# LEDs.net
KiCad netlist of a schematic drawn in Altium Designer
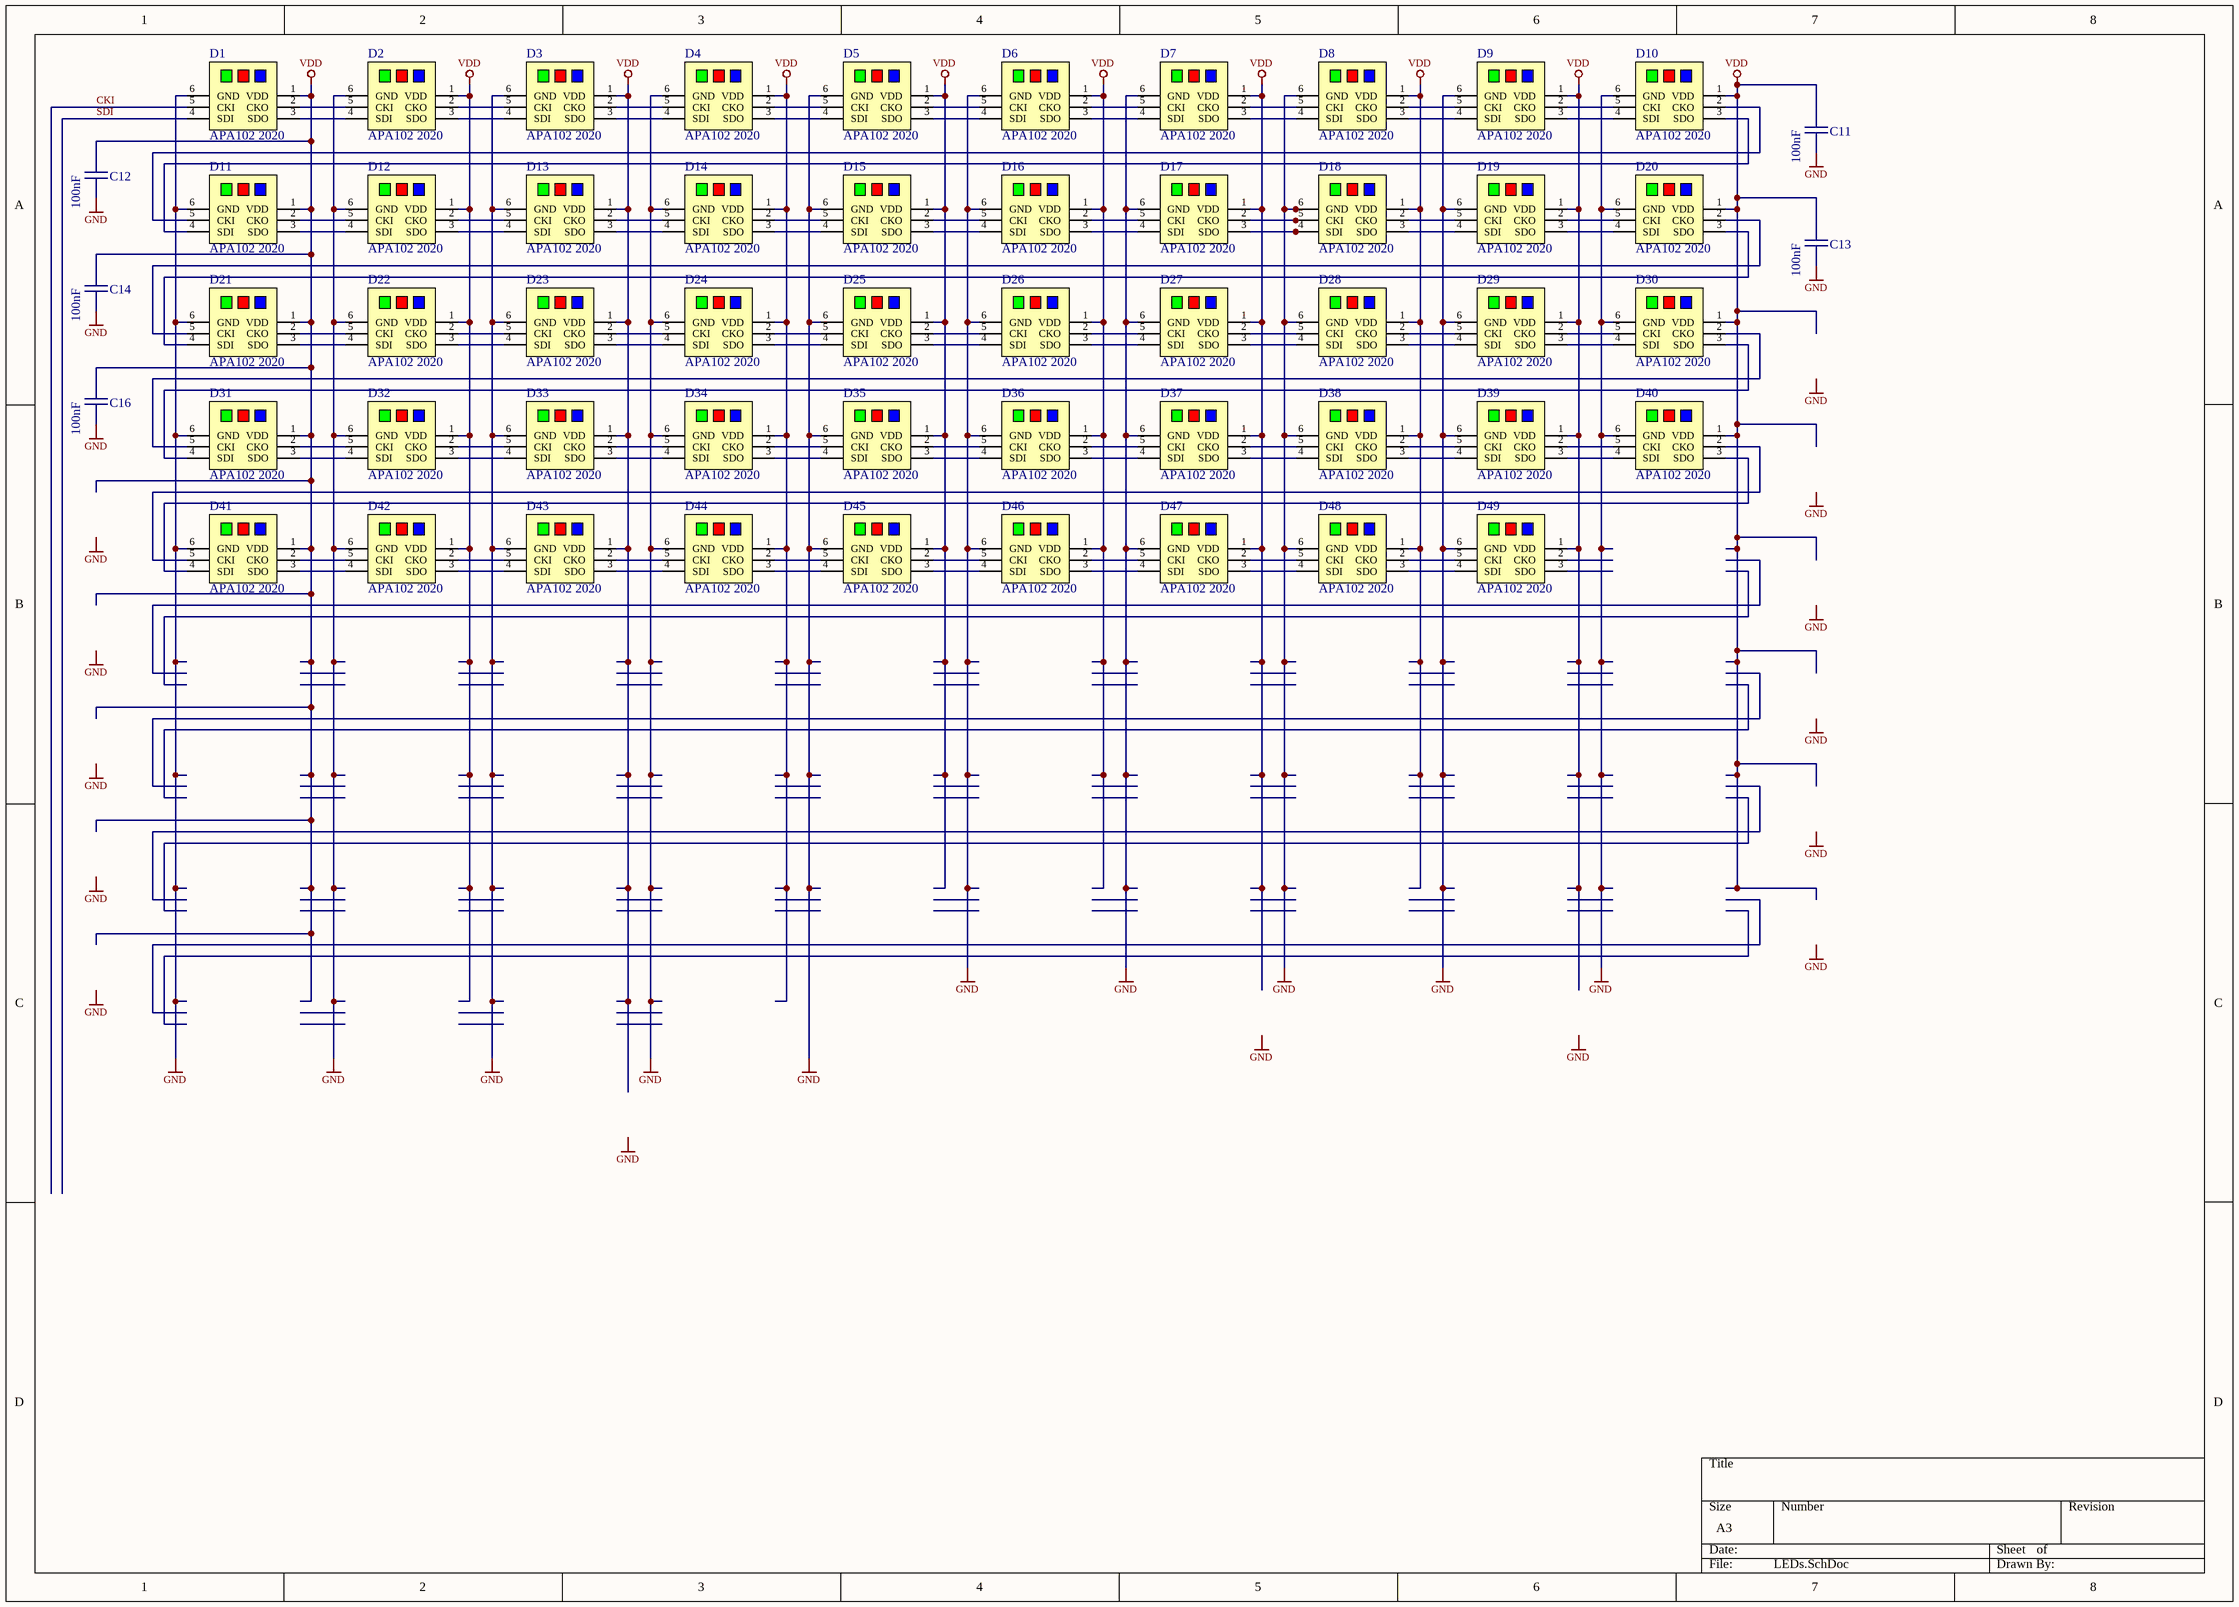
[diagram p0: LEDs.SchDoc]

(export (version "E")
  (design (tool "Eeschema 10.0.6"))
  (components
    (comp (ref "C11")
      (value "100nF")
      (footprint "CAPC0603(1608)55_N")
      (libsource (lib "OVLib_64") (part "CAP"))
    )
    (comp (ref "C12")
      (value "100nF")
      (footprint "CAPC0603(1608)55_N")
      (libsource (lib "OVLib_64") (part "CAP"))
    )
    (comp (ref "C13")
      (value "100nF")
      (footprint "CAPC0603(1608)55_N")
      (libsource (lib "OVLib_64") (part "CAP"))
    )
    (comp (ref "C14")
      (value "100nF")
      (footprint "CAPC0603(1608)55_N")
      (libsource (lib "OVLib_64") (part "CAP"))
    )
    (comp (ref "C16")
      (value "100nF")
      (footprint "CAPC0603(1608)55_N")
      (libsource (lib "OVLib_64") (part "CAP"))
    )
    (comp (ref "D1")
      (value "APA102 2020")
      (footprint "APA_RGB_LED_2020")
      (libsource (lib "OVLib_64") (part "LED_RGB_APA102"))
    )
    (comp (ref "D2")
      (value "APA102 2020")
      (footprint "APA_RGB_LED_2020")
      (libsource (lib "OVLib_64") (part "LED_RGB_APA102"))
    )
    (comp (ref "D3")
      (value "APA102 2020")
      (footprint "APA_RGB_LED_2020")
      (libsource (lib "OVLib_64") (part "LED_RGB_APA102"))
    )
    (comp (ref "D4")
      (value "APA102 2020")
      (footprint "APA_RGB_LED_2020")
      (libsource (lib "OVLib_64") (part "LED_RGB_APA102"))
    )
    (comp (ref "D5")
      (value "APA102 2020")
      (footprint "APA_RGB_LED_2020")
      (libsource (lib "OVLib_64") (part "LED_RGB_APA102"))
    )
    (comp (ref "D6")
      (value "APA102 2020")
      (footprint "APA_RGB_LED_2020")
      (libsource (lib "OVLib_64") (part "LED_RGB_APA102"))
    )
    (comp (ref "D7")
      (value "APA102 2020")
      (footprint "APA_RGB_LED_2020")
      (libsource (lib "OVLib_64") (part "LED_RGB_APA102"))
    )
    (comp (ref "D8")
      (value "APA102 2020")
      (footprint "APA_RGB_LED_2020")
      (libsource (lib "OVLib_64") (part "LED_RGB_APA102"))
    )
    (comp (ref "D9")
      (value "APA102 2020")
      (footprint "APA_RGB_LED_2020")
      (libsource (lib "OVLib_64") (part "LED_RGB_APA102"))
    )
    (comp (ref "D10")
      (value "APA102 2020")
      (footprint "APA_RGB_LED_2020")
      (libsource (lib "OVLib_64") (part "LED_RGB_APA102"))
    )
    (comp (ref "D11")
      (value "APA102 2020")
      (footprint "APA_RGB_LED_2020")
      (libsource (lib "OVLib_64") (part "LED_RGB_APA102"))
    )
    (comp (ref "D12")
      (value "APA102 2020")
      (footprint "APA_RGB_LED_2020")
      (libsource (lib "OVLib_64") (part "LED_RGB_APA102"))
    )
    (comp (ref "D13")
      (value "APA102 2020")
      (footprint "APA_RGB_LED_2020")
      (libsource (lib "OVLib_64") (part "LED_RGB_APA102"))
    )
    (comp (ref "D14")
      (value "APA102 2020")
      (footprint "APA_RGB_LED_2020")
      (libsource (lib "OVLib_64") (part "LED_RGB_APA102"))
    )
    (comp (ref "D15")
      (value "APA102 2020")
      (footprint "APA_RGB_LED_2020")
      (libsource (lib "OVLib_64") (part "LED_RGB_APA102"))
    )
    (comp (ref "D16")
      (value "APA102 2020")
      (footprint "APA_RGB_LED_2020")
      (libsource (lib "OVLib_64") (part "LED_RGB_APA102"))
    )
    (comp (ref "D17")
      (value "APA102 2020")
      (footprint "APA_RGB_LED_2020")
      (libsource (lib "OVLib_64") (part "LED_RGB_APA102"))
    )
    (comp (ref "D18")
      (value "APA102 2020")
      (footprint "APA_RGB_LED_2020")
      (libsource (lib "OVLib_64") (part "LED_RGB_APA102"))
    )
    (comp (ref "D19")
      (value "APA102 2020")
      (footprint "APA_RGB_LED_2020")
      (libsource (lib "OVLib_64") (part "LED_RGB_APA102"))
    )
    (comp (ref "D20")
      (value "APA102 2020")
      (footprint "APA_RGB_LED_2020")
      (libsource (lib "OVLib_64") (part "LED_RGB_APA102"))
    )
    (comp (ref "D21")
      (value "APA102 2020")
      (footprint "APA_RGB_LED_2020")
      (libsource (lib "OVLib_64") (part "LED_RGB_APA102"))
    )
    (comp (ref "D22")
      (value "APA102 2020")
      (footprint "APA_RGB_LED_2020")
      (libsource (lib "OVLib_64") (part "LED_RGB_APA102"))
    )
    (comp (ref "D23")
      (value "APA102 2020")
      (footprint "APA_RGB_LED_2020")
      (libsource (lib "OVLib_64") (part "LED_RGB_APA102"))
    )
    (comp (ref "D24")
      (value "APA102 2020")
      (footprint "APA_RGB_LED_2020")
      (libsource (lib "OVLib_64") (part "LED_RGB_APA102"))
    )
    (comp (ref "D25")
      (value "APA102 2020")
      (footprint "APA_RGB_LED_2020")
      (libsource (lib "OVLib_64") (part "LED_RGB_APA102"))
    )
    (comp (ref "D26")
      (value "APA102 2020")
      (footprint "APA_RGB_LED_2020")
      (libsource (lib "OVLib_64") (part "LED_RGB_APA102"))
    )
    (comp (ref "D27")
      (value "APA102 2020")
      (footprint "APA_RGB_LED_2020")
      (libsource (lib "OVLib_64") (part "LED_RGB_APA102"))
    )
    (comp (ref "D28")
      (value "APA102 2020")
      (footprint "APA_RGB_LED_2020")
      (libsource (lib "OVLib_64") (part "LED_RGB_APA102"))
    )
    (comp (ref "D29")
      (value "APA102 2020")
      (footprint "APA_RGB_LED_2020")
      (libsource (lib "OVLib_64") (part "LED_RGB_APA102"))
    )
    (comp (ref "D30")
      (value "APA102 2020")
      (footprint "APA_RGB_LED_2020")
      (libsource (lib "OVLib_64") (part "LED_RGB_APA102"))
    )
    (comp (ref "D31")
      (value "APA102 2020")
      (footprint "APA_RGB_LED_2020")
      (libsource (lib "OVLib_64") (part "LED_RGB_APA102"))
    )
    (comp (ref "D32")
      (value "APA102 2020")
      (footprint "APA_RGB_LED_2020")
      (libsource (lib "OVLib_64") (part "LED_RGB_APA102"))
    )
    (comp (ref "D33")
      (value "APA102 2020")
      (footprint "APA_RGB_LED_2020")
      (libsource (lib "OVLib_64") (part "LED_RGB_APA102"))
    )
    (comp (ref "D34")
      (value "APA102 2020")
      (footprint "APA_RGB_LED_2020")
      (libsource (lib "OVLib_64") (part "LED_RGB_APA102"))
    )
    (comp (ref "D35")
      (value "APA102 2020")
      (footprint "APA_RGB_LED_2020")
      (libsource (lib "OVLib_64") (part "LED_RGB_APA102"))
    )
    (comp (ref "D36")
      (value "APA102 2020")
      (footprint "APA_RGB_LED_2020")
      (libsource (lib "OVLib_64") (part "LED_RGB_APA102"))
    )
    (comp (ref "D37")
      (value "APA102 2020")
      (footprint "APA_RGB_LED_2020")
      (libsource (lib "OVLib_64") (part "LED_RGB_APA102"))
    )
    (comp (ref "D38")
      (value "APA102 2020")
      (footprint "APA_RGB_LED_2020")
      (libsource (lib "OVLib_64") (part "LED_RGB_APA102"))
    )
    (comp (ref "D39")
      (value "APA102 2020")
      (footprint "APA_RGB_LED_2020")
      (libsource (lib "OVLib_64") (part "LED_RGB_APA102"))
    )
    (comp (ref "D40")
      (value "APA102 2020")
      (footprint "APA_RGB_LED_2020")
      (libsource (lib "OVLib_64") (part "LED_RGB_APA102"))
    )
    (comp (ref "D41")
      (value "APA102 2020")
      (footprint "APA_RGB_LED_2020")
      (libsource (lib "OVLib_64") (part "LED_RGB_APA102"))
    )
    (comp (ref "D42")
      (value "APA102 2020")
      (footprint "APA_RGB_LED_2020")
      (libsource (lib "OVLib_64") (part "LED_RGB_APA102"))
    )
    (comp (ref "D43")
      (value "APA102 2020")
      (footprint "APA_RGB_LED_2020")
      (libsource (lib "OVLib_64") (part "LED_RGB_APA102"))
    )
    (comp (ref "D44")
      (value "APA102 2020")
      (footprint "APA_RGB_LED_2020")
      (libsource (lib "OVLib_64") (part "LED_RGB_APA102"))
    )
    (comp (ref "D45")
      (value "APA102 2020")
      (footprint "APA_RGB_LED_2020")
      (libsource (lib "OVLib_64") (part "LED_RGB_APA102"))
    )
    (comp (ref "D46")
      (value "APA102 2020")
      (footprint "APA_RGB_LED_2020")
      (libsource (lib "OVLib_64") (part "LED_RGB_APA102"))
    )
    (comp (ref "D47")
      (value "APA102 2020")
      (footprint "APA_RGB_LED_2020")
      (libsource (lib "OVLib_64") (part "LED_RGB_APA102"))
    )
    (comp (ref "D48")
      (value "APA102 2020")
      (footprint "APA_RGB_LED_2020")
      (libsource (lib "OVLib_64") (part "LED_RGB_APA102"))
    )
    (comp (ref "D49")
      (value "APA102 2020")
      (footprint "APA_RGB_LED_2020")
      (libsource (lib "OVLib_64") (part "LED_RGB_APA102"))
    )
  )
  (nets
    (net (code "1") (name "/CKI") (class "Default")
      (node (ref "D1") (pin "5") (pinfunction "CKI_5") (pintype "passive"))
    )
    (net (code "2") (name "/SDI") (class "Default")
      (node (ref "D1") (pin "4") (pinfunction "SDI_4") (pintype "passive"))
    )
    (net (code "3") (name "GND") (class "Default")
      (node (ref "C11") (pin "1") (pinfunction "1_1") (pintype "passive"))
      (node (ref "C12") (pin "1") (pinfunction "1_1") (pintype "passive"))
      (node (ref "C13") (pin "1") (pinfunction "1_1") (pintype "passive"))
      (node (ref "C14") (pin "1") (pinfunction "1_1") (pintype "passive"))
      (node (ref "C16") (pin "1") (pinfunction "1_1") (pintype "passive"))
      (node (ref "D1") (pin "6") (pinfunction "GND_6") (pintype "passive"))
      (node (ref "D10") (pin "6") (pinfunction "GND_6") (pintype "passive"))
      (node (ref "D11") (pin "6") (pinfunction "GND_6") (pintype "passive"))
      (node (ref "D12") (pin "6") (pinfunction "GND_6") (pintype "passive"))
      (node (ref "D13") (pin "6") (pinfunction "GND_6") (pintype "passive"))
      (node (ref "D14") (pin "6") (pinfunction "GND_6") (pintype "passive"))
      (node (ref "D15") (pin "6") (pinfunction "GND_6") (pintype "passive"))
      (node (ref "D16") (pin "6") (pinfunction "GND_6") (pintype "passive"))
      (node (ref "D17") (pin "6") (pinfunction "GND_6") (pintype "passive"))
      (node (ref "D18") (pin "6") (pinfunction "GND_6") (pintype "passive"))
      (node (ref "D19") (pin "6") (pinfunction "GND_6") (pintype "passive"))
      (node (ref "D2") (pin "6") (pinfunction "GND_6") (pintype "passive"))
      (node (ref "D20") (pin "6") (pinfunction "GND_6") (pintype "passive"))
      (node (ref "D21") (pin "6") (pinfunction "GND_6") (pintype "passive"))
      (node (ref "D22") (pin "6") (pinfunction "GND_6") (pintype "passive"))
      (node (ref "D23") (pin "6") (pinfunction "GND_6") (pintype "passive"))
      (node (ref "D24") (pin "6") (pinfunction "GND_6") (pintype "passive"))
      (node (ref "D25") (pin "6") (pinfunction "GND_6") (pintype "passive"))
      (node (ref "D26") (pin "6") (pinfunction "GND_6") (pintype "passive"))
      (node (ref "D27") (pin "6") (pinfunction "GND_6") (pintype "passive"))
      (node (ref "D28") (pin "6") (pinfunction "GND_6") (pintype "passive"))
      (node (ref "D29") (pin "6") (pinfunction "GND_6") (pintype "passive"))
      (node (ref "D3") (pin "6") (pinfunction "GND_6") (pintype "passive"))
      (node (ref "D30") (pin "6") (pinfunction "GND_6") (pintype "passive"))
      (node (ref "D31") (pin "6") (pinfunction "GND_6") (pintype "passive"))
      (node (ref "D32") (pin "6") (pinfunction "GND_6") (pintype "passive"))
      (node (ref "D33") (pin "6") (pinfunction "GND_6") (pintype "passive"))
      (node (ref "D34") (pin "6") (pinfunction "GND_6") (pintype "passive"))
      (node (ref "D35") (pin "6") (pinfunction "GND_6") (pintype "passive"))
      (node (ref "D36") (pin "6") (pinfunction "GND_6") (pintype "passive"))
      (node (ref "D37") (pin "6") (pinfunction "GND_6") (pintype "passive"))
      (node (ref "D38") (pin "6") (pinfunction "GND_6") (pintype "passive"))
      (node (ref "D39") (pin "6") (pinfunction "GND_6") (pintype "passive"))
      (node (ref "D4") (pin "6") (pinfunction "GND_6") (pintype "passive"))
      (node (ref "D40") (pin "6") (pinfunction "GND_6") (pintype "passive"))
      (node (ref "D41") (pin "6") (pinfunction "GND_6") (pintype "passive"))
      (node (ref "D42") (pin "6") (pinfunction "GND_6") (pintype "passive"))
      (node (ref "D43") (pin "6") (pinfunction "GND_6") (pintype "passive"))
      (node (ref "D44") (pin "6") (pinfunction "GND_6") (pintype "passive"))
      (node (ref "D45") (pin "6") (pinfunction "GND_6") (pintype "passive"))
      (node (ref "D46") (pin "6") (pinfunction "GND_6") (pintype "passive"))
      (node (ref "D47") (pin "6") (pinfunction "GND_6") (pintype "passive"))
      (node (ref "D48") (pin "6") (pinfunction "GND_6") (pintype "passive"))
      (node (ref "D49") (pin "6") (pinfunction "GND_6") (pintype "passive"))
      (node (ref "D5") (pin "6") (pinfunction "GND_6") (pintype "passive"))
      (node (ref "D6") (pin "6") (pinfunction "GND_6") (pintype "passive"))
      (node (ref "D7") (pin "6") (pinfunction "GND_6") (pintype "passive"))
      (node (ref "D8") (pin "6") (pinfunction "GND_6") (pintype "passive"))
      (node (ref "D9") (pin "6") (pinfunction "GND_6") (pintype "passive"))
    )
    (net (code "4") (name "Net-(D1-CKO)") (class "Default")
      (node (ref "D1") (pin "2") (pinfunction "CKO_2") (pintype "passive"))
      (node (ref "D2") (pin "5") (pinfunction "CKI_5") (pintype "passive"))
    )
    (net (code "5") (name "Net-(D1-SDO)") (class "Default")
      (node (ref "D1") (pin "3") (pinfunction "SDO_3") (pintype "passive"))
      (node (ref "D2") (pin "4") (pinfunction "SDI_4") (pintype "passive"))
    )
    (net (code "6") (name "Net-(D2-CKO)") (class "Default")
      (node (ref "D2") (pin "2") (pinfunction "CKO_2") (pintype "passive"))
      (node (ref "D3") (pin "5") (pinfunction "CKI_5") (pintype "passive"))
    )
    (net (code "7") (name "Net-(D2-SDO)") (class "Default")
      (node (ref "D2") (pin "3") (pinfunction "SDO_3") (pintype "passive"))
      (node (ref "D3") (pin "4") (pinfunction "SDI_4") (pintype "passive"))
    )
    (net (code "8") (name "Net-(D3-CKO)") (class "Default")
      (node (ref "D3") (pin "2") (pinfunction "CKO_2") (pintype "passive"))
      (node (ref "D4") (pin "5") (pinfunction "CKI_5") (pintype "passive"))
    )
    (net (code "9") (name "Net-(D3-SDO)") (class "Default")
      (node (ref "D3") (pin "3") (pinfunction "SDO_3") (pintype "passive"))
      (node (ref "D4") (pin "4") (pinfunction "SDI_4") (pintype "passive"))
    )
    (net (code "10") (name "Net-(D4-CKO)") (class "Default")
      (node (ref "D4") (pin "2") (pinfunction "CKO_2") (pintype "passive"))
      (node (ref "D5") (pin "5") (pinfunction "CKI_5") (pintype "passive"))
    )
    (net (code "11") (name "Net-(D4-SDO)") (class "Default")
      (node (ref "D4") (pin "3") (pinfunction "SDO_3") (pintype "passive"))
      (node (ref "D5") (pin "4") (pinfunction "SDI_4") (pintype "passive"))
    )
    (net (code "12") (name "Net-(D5-CKO)") (class "Default")
      (node (ref "D5") (pin "2") (pinfunction "CKO_2") (pintype "passive"))
      (node (ref "D6") (pin "5") (pinfunction "CKI_5") (pintype "passive"))
    )
    (net (code "13") (name "Net-(D5-SDO)") (class "Default")
      (node (ref "D5") (pin "3") (pinfunction "SDO_3") (pintype "passive"))
      (node (ref "D6") (pin "4") (pinfunction "SDI_4") (pintype "passive"))
    )
    (net (code "14") (name "Net-(D6-CKO)") (class "Default")
      (node (ref "D6") (pin "2") (pinfunction "CKO_2") (pintype "passive"))
      (node (ref "D7") (pin "5") (pinfunction "CKI_5") (pintype "passive"))
    )
    (net (code "15") (name "Net-(D6-SDO)") (class "Default")
      (node (ref "D6") (pin "3") (pinfunction "SDO_3") (pintype "passive"))
      (node (ref "D7") (pin "4") (pinfunction "SDI_4") (pintype "passive"))
    )
    (net (code "16") (name "Net-(D7-CKO)") (class "Default")
      (node (ref "D7") (pin "2") (pinfunction "CKO_2") (pintype "passive"))
      (node (ref "D8") (pin "5") (pinfunction "CKI_5") (pintype "passive"))
    )
    (net (code "17") (name "Net-(D7-SDO)") (class "Default")
      (node (ref "D7") (pin "3") (pinfunction "SDO_3") (pintype "passive"))
      (node (ref "D8") (pin "4") (pinfunction "SDI_4") (pintype "passive"))
    )
    (net (code "18") (name "Net-(D8-CKO)") (class "Default")
      (node (ref "D8") (pin "2") (pinfunction "CKO_2") (pintype "passive"))
      (node (ref "D9") (pin "5") (pinfunction "CKI_5") (pintype "passive"))
    )
    (net (code "19") (name "Net-(D8-SDO)") (class "Default")
      (node (ref "D8") (pin "3") (pinfunction "SDO_3") (pintype "passive"))
      (node (ref "D9") (pin "4") (pinfunction "SDI_4") (pintype "passive"))
    )
    (net (code "20") (name "Net-(D10-CKI)") (class "Default")
      (node (ref "D10") (pin "5") (pinfunction "CKI_5") (pintype "passive"))
      (node (ref "D9") (pin "2") (pinfunction "CKO_2") (pintype "passive"))
    )
    (net (code "21") (name "Net-(D10-CKO)") (class "Default")
      (node (ref "D10") (pin "2") (pinfunction "CKO_2") (pintype "passive"))
      (node (ref "D11") (pin "5") (pinfunction "CKI_5") (pintype "passive"))
    )
    (net (code "22") (name "Net-(D10-SDI)") (class "Default")
      (node (ref "D10") (pin "4") (pinfunction "SDI_4") (pintype "passive"))
      (node (ref "D9") (pin "3") (pinfunction "SDO_3") (pintype "passive"))
    )
    (net (code "23") (name "Net-(D10-SDO)") (class "Default")
      (node (ref "D10") (pin "3") (pinfunction "SDO_3") (pintype "passive"))
      (node (ref "D11") (pin "4") (pinfunction "SDI_4") (pintype "passive"))
    )
    (net (code "24") (name "Net-(D11-CKO)") (class "Default")
      (node (ref "D11") (pin "2") (pinfunction "CKO_2") (pintype "passive"))
      (node (ref "D12") (pin "5") (pinfunction "CKI_5") (pintype "passive"))
    )
    (net (code "25") (name "Net-(D11-SDO)") (class "Default")
      (node (ref "D11") (pin "3") (pinfunction "SDO_3") (pintype "passive"))
      (node (ref "D12") (pin "4") (pinfunction "SDI_4") (pintype "passive"))
    )
    (net (code "26") (name "Net-(D12-CKO)") (class "Default")
      (node (ref "D12") (pin "2") (pinfunction "CKO_2") (pintype "passive"))
      (node (ref "D13") (pin "5") (pinfunction "CKI_5") (pintype "passive"))
    )
    (net (code "27") (name "Net-(D12-SDO)") (class "Default")
      (node (ref "D12") (pin "3") (pinfunction "SDO_3") (pintype "passive"))
      (node (ref "D13") (pin "4") (pinfunction "SDI_4") (pintype "passive"))
    )
    (net (code "28") (name "Net-(D13-CKO)") (class "Default")
      (node (ref "D13") (pin "2") (pinfunction "CKO_2") (pintype "passive"))
      (node (ref "D14") (pin "5") (pinfunction "CKI_5") (pintype "passive"))
    )
    (net (code "29") (name "Net-(D13-SDO)") (class "Default")
      (node (ref "D13") (pin "3") (pinfunction "SDO_3") (pintype "passive"))
      (node (ref "D14") (pin "4") (pinfunction "SDI_4") (pintype "passive"))
    )
    (net (code "30") (name "Net-(D14-CKO)") (class "Default")
      (node (ref "D14") (pin "2") (pinfunction "CKO_2") (pintype "passive"))
      (node (ref "D15") (pin "5") (pinfunction "CKI_5") (pintype "passive"))
    )
    (net (code "31") (name "Net-(D14-SDO)") (class "Default")
      (node (ref "D14") (pin "3") (pinfunction "SDO_3") (pintype "passive"))
      (node (ref "D15") (pin "4") (pinfunction "SDI_4") (pintype "passive"))
    )
    (net (code "32") (name "Net-(D15-CKO)") (class "Default")
      (node (ref "D15") (pin "2") (pinfunction "CKO_2") (pintype "passive"))
      (node (ref "D16") (pin "5") (pinfunction "CKI_5") (pintype "passive"))
    )
    (net (code "33") (name "Net-(D15-SDO)") (class "Default")
      (node (ref "D15") (pin "3") (pinfunction "SDO_3") (pintype "passive"))
      (node (ref "D16") (pin "4") (pinfunction "SDI_4") (pintype "passive"))
    )
    (net (code "34") (name "Net-(D16-CKO)") (class "Default")
      (node (ref "D16") (pin "2") (pinfunction "CKO_2") (pintype "passive"))
      (node (ref "D17") (pin "5") (pinfunction "CKI_5") (pintype "passive"))
    )
    (net (code "35") (name "Net-(D16-SDO)") (class "Default")
      (node (ref "D16") (pin "3") (pinfunction "SDO_3") (pintype "passive"))
      (node (ref "D17") (pin "4") (pinfunction "SDI_4") (pintype "passive"))
    )
    (net (code "36") (name "Net-(D17-CKO)") (class "Default")
      (node (ref "D17") (pin "2") (pinfunction "CKO_2") (pintype "passive"))
      (node (ref "D18") (pin "5") (pinfunction "CKI_5") (pintype "passive"))
    )
    (net (code "37") (name "Net-(D17-SDO)") (class "Default")
      (node (ref "D17") (pin "3") (pinfunction "SDO_3") (pintype "passive"))
      (node (ref "D18") (pin "4") (pinfunction "SDI_4") (pintype "passive"))
    )
    (net (code "38") (name "Net-(D18-CKO)") (class "Default")
      (node (ref "D18") (pin "2") (pinfunction "CKO_2") (pintype "passive"))
      (node (ref "D19") (pin "5") (pinfunction "CKI_5") (pintype "passive"))
    )
    (net (code "39") (name "Net-(D18-SDO)") (class "Default")
      (node (ref "D18") (pin "3") (pinfunction "SDO_3") (pintype "passive"))
      (node (ref "D19") (pin "4") (pinfunction "SDI_4") (pintype "passive"))
    )
    (net (code "40") (name "Net-(D19-CKO)") (class "Default")
      (node (ref "D19") (pin "2") (pinfunction "CKO_2") (pintype "passive"))
      (node (ref "D20") (pin "5") (pinfunction "CKI_5") (pintype "passive"))
    )
    (net (code "41") (name "Net-(D19-SDO)") (class "Default")
      (node (ref "D19") (pin "3") (pinfunction "SDO_3") (pintype "passive"))
      (node (ref "D20") (pin "4") (pinfunction "SDI_4") (pintype "passive"))
    )
    (net (code "42") (name "Net-(D20-CKO)") (class "Default")
      (node (ref "D20") (pin "2") (pinfunction "CKO_2") (pintype "passive"))
      (node (ref "D21") (pin "5") (pinfunction "CKI_5") (pintype "passive"))
    )
    (net (code "43") (name "Net-(D20-SDO)") (class "Default")
      (node (ref "D20") (pin "3") (pinfunction "SDO_3") (pintype "passive"))
      (node (ref "D21") (pin "4") (pinfunction "SDI_4") (pintype "passive"))
    )
    (net (code "44") (name "Net-(D21-CKO)") (class "Default")
      (node (ref "D21") (pin "2") (pinfunction "CKO_2") (pintype "passive"))
      (node (ref "D22") (pin "5") (pinfunction "CKI_5") (pintype "passive"))
    )
    (net (code "45") (name "Net-(D21-SDO)") (class "Default")
      (node (ref "D21") (pin "3") (pinfunction "SDO_3") (pintype "passive"))
      (node (ref "D22") (pin "4") (pinfunction "SDI_4") (pintype "passive"))
    )
    (net (code "46") (name "Net-(D22-CKO)") (class "Default")
      (node (ref "D22") (pin "2") (pinfunction "CKO_2") (pintype "passive"))
      (node (ref "D23") (pin "5") (pinfunction "CKI_5") (pintype "passive"))
    )
    (net (code "47") (name "Net-(D22-SDO)") (class "Default")
      (node (ref "D22") (pin "3") (pinfunction "SDO_3") (pintype "passive"))
      (node (ref "D23") (pin "4") (pinfunction "SDI_4") (pintype "passive"))
    )
    (net (code "48") (name "Net-(D23-CKO)") (class "Default")
      (node (ref "D23") (pin "2") (pinfunction "CKO_2") (pintype "passive"))
      (node (ref "D24") (pin "5") (pinfunction "CKI_5") (pintype "passive"))
    )
    (net (code "49") (name "Net-(D23-SDO)") (class "Default")
      (node (ref "D23") (pin "3") (pinfunction "SDO_3") (pintype "passive"))
      (node (ref "D24") (pin "4") (pinfunction "SDI_4") (pintype "passive"))
    )
    (net (code "50") (name "Net-(D24-CKO)") (class "Default")
      (node (ref "D24") (pin "2") (pinfunction "CKO_2") (pintype "passive"))
      (node (ref "D25") (pin "5") (pinfunction "CKI_5") (pintype "passive"))
    )
    (net (code "51") (name "Net-(D24-SDO)") (class "Default")
      (node (ref "D24") (pin "3") (pinfunction "SDO_3") (pintype "passive"))
      (node (ref "D25") (pin "4") (pinfunction "SDI_4") (pintype "passive"))
    )
    (net (code "52") (name "Net-(D25-CKO)") (class "Default")
      (node (ref "D25") (pin "2") (pinfunction "CKO_2") (pintype "passive"))
      (node (ref "D26") (pin "5") (pinfunction "CKI_5") (pintype "passive"))
    )
    (net (code "53") (name "Net-(D25-SDO)") (class "Default")
      (node (ref "D25") (pin "3") (pinfunction "SDO_3") (pintype "passive"))
      (node (ref "D26") (pin "4") (pinfunction "SDI_4") (pintype "passive"))
    )
    (net (code "54") (name "Net-(D26-CKO)") (class "Default")
      (node (ref "D26") (pin "2") (pinfunction "CKO_2") (pintype "passive"))
      (node (ref "D27") (pin "5") (pinfunction "CKI_5") (pintype "passive"))
    )
    (net (code "55") (name "Net-(D26-SDO)") (class "Default")
      (node (ref "D26") (pin "3") (pinfunction "SDO_3") (pintype "passive"))
      (node (ref "D27") (pin "4") (pinfunction "SDI_4") (pintype "passive"))
    )
    (net (code "56") (name "Net-(D27-CKO)") (class "Default")
      (node (ref "D27") (pin "2") (pinfunction "CKO_2") (pintype "passive"))
      (node (ref "D28") (pin "5") (pinfunction "CKI_5") (pintype "passive"))
    )
    (net (code "57") (name "Net-(D27-SDO)") (class "Default")
      (node (ref "D27") (pin "3") (pinfunction "SDO_3") (pintype "passive"))
      (node (ref "D28") (pin "4") (pinfunction "SDI_4") (pintype "passive"))
    )
    (net (code "58") (name "Net-(D28-CKO)") (class "Default")
      (node (ref "D28") (pin "2") (pinfunction "CKO_2") (pintype "passive"))
      (node (ref "D29") (pin "5") (pinfunction "CKI_5") (pintype "passive"))
    )
    (net (code "59") (name "Net-(D28-SDO)") (class "Default")
      (node (ref "D28") (pin "3") (pinfunction "SDO_3") (pintype "passive"))
      (node (ref "D29") (pin "4") (pinfunction "SDI_4") (pintype "passive"))
    )
    (net (code "60") (name "Net-(D29-CKO)") (class "Default")
      (node (ref "D29") (pin "2") (pinfunction "CKO_2") (pintype "passive"))
      (node (ref "D30") (pin "5") (pinfunction "CKI_5") (pintype "passive"))
    )
    (net (code "61") (name "Net-(D29-SDO)") (class "Default")
      (node (ref "D29") (pin "3") (pinfunction "SDO_3") (pintype "passive"))
      (node (ref "D30") (pin "4") (pinfunction "SDI_4") (pintype "passive"))
    )
    (net (code "62") (name "Net-(D30-CKO)") (class "Default")
      (node (ref "D30") (pin "2") (pinfunction "CKO_2") (pintype "passive"))
      (node (ref "D31") (pin "5") (pinfunction "CKI_5") (pintype "passive"))
    )
    (net (code "63") (name "Net-(D30-SDO)") (class "Default")
      (node (ref "D30") (pin "3") (pinfunction "SDO_3") (pintype "passive"))
      (node (ref "D31") (pin "4") (pinfunction "SDI_4") (pintype "passive"))
    )
    (net (code "64") (name "Net-(D31-CKO)") (class "Default")
      (node (ref "D31") (pin "2") (pinfunction "CKO_2") (pintype "passive"))
      (node (ref "D32") (pin "5") (pinfunction "CKI_5") (pintype "passive"))
    )
    (net (code "65") (name "Net-(D31-SDO)") (class "Default")
      (node (ref "D31") (pin "3") (pinfunction "SDO_3") (pintype "passive"))
      (node (ref "D32") (pin "4") (pinfunction "SDI_4") (pintype "passive"))
    )
    (net (code "66") (name "Net-(D32-CKO)") (class "Default")
      (node (ref "D32") (pin "2") (pinfunction "CKO_2") (pintype "passive"))
      (node (ref "D33") (pin "5") (pinfunction "CKI_5") (pintype "passive"))
    )
    (net (code "67") (name "Net-(D32-SDO)") (class "Default")
      (node (ref "D32") (pin "3") (pinfunction "SDO_3") (pintype "passive"))
      (node (ref "D33") (pin "4") (pinfunction "SDI_4") (pintype "passive"))
    )
    (net (code "68") (name "Net-(D33-CKO)") (class "Default")
      (node (ref "D33") (pin "2") (pinfunction "CKO_2") (pintype "passive"))
      (node (ref "D34") (pin "5") (pinfunction "CKI_5") (pintype "passive"))
    )
    (net (code "69") (name "Net-(D33-SDO)") (class "Default")
      (node (ref "D33") (pin "3") (pinfunction "SDO_3") (pintype "passive"))
      (node (ref "D34") (pin "4") (pinfunction "SDI_4") (pintype "passive"))
    )
    (net (code "70") (name "Net-(D34-CKO)") (class "Default")
      (node (ref "D34") (pin "2") (pinfunction "CKO_2") (pintype "passive"))
      (node (ref "D35") (pin "5") (pinfunction "CKI_5") (pintype "passive"))
    )
    (net (code "71") (name "Net-(D34-SDO)") (class "Default")
      (node (ref "D34") (pin "3") (pinfunction "SDO_3") (pintype "passive"))
      (node (ref "D35") (pin "4") (pinfunction "SDI_4") (pintype "passive"))
    )
    (net (code "72") (name "Net-(D35-CKO)") (class "Default")
      (node (ref "D35") (pin "2") (pinfunction "CKO_2") (pintype "passive"))
      (node (ref "D36") (pin "5") (pinfunction "CKI_5") (pintype "passive"))
    )
    (net (code "73") (name "Net-(D35-SDO)") (class "Default")
      (node (ref "D35") (pin "3") (pinfunction "SDO_3") (pintype "passive"))
      (node (ref "D36") (pin "4") (pinfunction "SDI_4") (pintype "passive"))
    )
    (net (code "74") (name "Net-(D36-CKO)") (class "Default")
      (node (ref "D36") (pin "2") (pinfunction "CKO_2") (pintype "passive"))
      (node (ref "D37") (pin "5") (pinfunction "CKI_5") (pintype "passive"))
    )
    (net (code "75") (name "Net-(D36-SDO)") (class "Default")
      (node (ref "D36") (pin "3") (pinfunction "SDO_3") (pintype "passive"))
      (node (ref "D37") (pin "4") (pinfunction "SDI_4") (pintype "passive"))
    )
    (net (code "76") (name "Net-(D37-CKO)") (class "Default")
      (node (ref "D37") (pin "2") (pinfunction "CKO_2") (pintype "passive"))
      (node (ref "D38") (pin "5") (pinfunction "CKI_5") (pintype "passive"))
    )
    (net (code "77") (name "Net-(D37-SDO)") (class "Default")
      (node (ref "D37") (pin "3") (pinfunction "SDO_3") (pintype "passive"))
      (node (ref "D38") (pin "4") (pinfunction "SDI_4") (pintype "passive"))
    )
    (net (code "78") (name "Net-(D38-CKO)") (class "Default")
      (node (ref "D38") (pin "2") (pinfunction "CKO_2") (pintype "passive"))
      (node (ref "D39") (pin "5") (pinfunction "CKI_5") (pintype "passive"))
    )
    (net (code "79") (name "Net-(D38-SDO)") (class "Default")
      (node (ref "D38") (pin "3") (pinfunction "SDO_3") (pintype "passive"))
      (node (ref "D39") (pin "4") (pinfunction "SDI_4") (pintype "passive"))
    )
    (net (code "80") (name "Net-(D39-CKO)") (class "Default")
      (node (ref "D39") (pin "2") (pinfunction "CKO_2") (pintype "passive"))
      (node (ref "D40") (pin "5") (pinfunction "CKI_5") (pintype "passive"))
    )
    (net (code "81") (name "Net-(D39-SDO)") (class "Default")
      (node (ref "D39") (pin "3") (pinfunction "SDO_3") (pintype "passive"))
      (node (ref "D40") (pin "4") (pinfunction "SDI_4") (pintype "passive"))
    )
    (net (code "82") (name "Net-(D40-CKO)") (class "Default")
      (node (ref "D40") (pin "2") (pinfunction "CKO_2") (pintype "passive"))
      (node (ref "D41") (pin "5") (pinfunction "CKI_5") (pintype "passive"))
    )
    (net (code "83") (name "Net-(D40-SDO)") (class "Default")
      (node (ref "D40") (pin "3") (pinfunction "SDO_3") (pintype "passive"))
      (node (ref "D41") (pin "4") (pinfunction "SDI_4") (pintype "passive"))
    )
    (net (code "84") (name "Net-(D41-CKO)") (class "Default")
      (node (ref "D41") (pin "2") (pinfunction "CKO_2") (pintype "passive"))
      (node (ref "D42") (pin "5") (pinfunction "CKI_5") (pintype "passive"))
    )
    (net (code "85") (name "Net-(D41-SDO)") (class "Default")
      (node (ref "D41") (pin "3") (pinfunction "SDO_3") (pintype "passive"))
      (node (ref "D42") (pin "4") (pinfunction "SDI_4") (pintype "passive"))
    )
    (net (code "86") (name "Net-(D42-CKO)") (class "Default")
      (node (ref "D42") (pin "2") (pinfunction "CKO_2") (pintype "passive"))
      (node (ref "D43") (pin "5") (pinfunction "CKI_5") (pintype "passive"))
    )
    (net (code "87") (name "Net-(D42-SDO)") (class "Default")
      (node (ref "D42") (pin "3") (pinfunction "SDO_3") (pintype "passive"))
      (node (ref "D43") (pin "4") (pinfunction "SDI_4") (pintype "passive"))
    )
    (net (code "88") (name "Net-(D43-CKO)") (class "Default")
      (node (ref "D43") (pin "2") (pinfunction "CKO_2") (pintype "passive"))
      (node (ref "D44") (pin "5") (pinfunction "CKI_5") (pintype "passive"))
    )
    (net (code "89") (name "Net-(D43-SDO)") (class "Default")
      (node (ref "D43") (pin "3") (pinfunction "SDO_3") (pintype "passive"))
      (node (ref "D44") (pin "4") (pinfunction "SDI_4") (pintype "passive"))
    )
    (net (code "90") (name "Net-(D44-CKO)") (class "Default")
      (node (ref "D44") (pin "2") (pinfunction "CKO_2") (pintype "passive"))
      (node (ref "D45") (pin "5") (pinfunction "CKI_5") (pintype "passive"))
    )
    (net (code "91") (name "Net-(D44-SDO)") (class "Default")
      (node (ref "D44") (pin "3") (pinfunction "SDO_3") (pintype "passive"))
      (node (ref "D45") (pin "4") (pinfunction "SDI_4") (pintype "passive"))
    )
    (net (code "92") (name "Net-(D45-CKO)") (class "Default")
      (node (ref "D45") (pin "2") (pinfunction "CKO_2") (pintype "passive"))
      (node (ref "D46") (pin "5") (pinfunction "CKI_5") (pintype "passive"))
    )
    (net (code "93") (name "Net-(D45-SDO)") (class "Default")
      (node (ref "D45") (pin "3") (pinfunction "SDO_3") (pintype "passive"))
      (node (ref "D46") (pin "4") (pinfunction "SDI_4") (pintype "passive"))
    )
    (net (code "94") (name "Net-(D46-CKO)") (class "Default")
      (node (ref "D46") (pin "2") (pinfunction "CKO_2") (pintype "passive"))
      (node (ref "D47") (pin "5") (pinfunction "CKI_5") (pintype "passive"))
    )
    (net (code "95") (name "Net-(D46-SDO)") (class "Default")
      (node (ref "D46") (pin "3") (pinfunction "SDO_3") (pintype "passive"))
      (node (ref "D47") (pin "4") (pinfunction "SDI_4") (pintype "passive"))
    )
    (net (code "96") (name "Net-(D47-CKO)") (class "Default")
      (node (ref "D47") (pin "2") (pinfunction "CKO_2") (pintype "passive"))
      (node (ref "D48") (pin "5") (pinfunction "CKI_5") (pintype "passive"))
    )
    (net (code "97") (name "Net-(D47-SDO)") (class "Default")
      (node (ref "D47") (pin "3") (pinfunction "SDO_3") (pintype "passive"))
      (node (ref "D48") (pin "4") (pinfunction "SDI_4") (pintype "passive"))
    )
    (net (code "98") (name "Net-(D48-CKO)") (class "Default")
      (node (ref "D48") (pin "2") (pinfunction "CKO_2") (pintype "passive"))
      (node (ref "D49") (pin "5") (pinfunction "CKI_5") (pintype "passive"))
    )
    (net (code "99") (name "Net-(D48-SDO)") (class "Default")
      (node (ref "D48") (pin "3") (pinfunction "SDO_3") (pintype "passive"))
      (node (ref "D49") (pin "4") (pinfunction "SDI_4") (pintype "passive"))
    )
    (net (code "100") (name "VDD") (class "Default")
      (node (ref "C11") (pin "2") (pinfunction "2_2") (pintype "passive"))
      (node (ref "C12") (pin "2") (pinfunction "2_2") (pintype "passive"))
      (node (ref "C13") (pin "2") (pinfunction "2_2") (pintype "passive"))
      (node (ref "C14") (pin "2") (pinfunction "2_2") (pintype "passive"))
      (node (ref "C16") (pin "2") (pinfunction "2_2") (pintype "passive"))
      (node (ref "D1") (pin "1") (pinfunction "VDD_1") (pintype "passive"))
      (node (ref "D10") (pin "1") (pinfunction "VDD_1") (pintype "passive"))
      (node (ref "D11") (pin "1") (pinfunction "VDD_1") (pintype "passive"))
      (node (ref "D12") (pin "1") (pinfunction "VDD_1") (pintype "passive"))
      (node (ref "D13") (pin "1") (pinfunction "VDD_1") (pintype "passive"))
      (node (ref "D14") (pin "1") (pinfunction "VDD_1") (pintype "passive"))
      (node (ref "D15") (pin "1") (pinfunction "VDD_1") (pintype "passive"))
      (node (ref "D16") (pin "1") (pinfunction "VDD_1") (pintype "passive"))
      (node (ref "D17") (pin "1") (pinfunction "VDD_1") (pintype "passive"))
      (node (ref "D18") (pin "1") (pinfunction "VDD_1") (pintype "passive"))
      (node (ref "D19") (pin "1") (pinfunction "VDD_1") (pintype "passive"))
      (node (ref "D2") (pin "1") (pinfunction "VDD_1") (pintype "passive"))
      (node (ref "D20") (pin "1") (pinfunction "VDD_1") (pintype "passive"))
      (node (ref "D21") (pin "1") (pinfunction "VDD_1") (pintype "passive"))
      (node (ref "D22") (pin "1") (pinfunction "VDD_1") (pintype "passive"))
      (node (ref "D23") (pin "1") (pinfunction "VDD_1") (pintype "passive"))
      (node (ref "D24") (pin "1") (pinfunction "VDD_1") (pintype "passive"))
      (node (ref "D25") (pin "1") (pinfunction "VDD_1") (pintype "passive"))
      (node (ref "D26") (pin "1") (pinfunction "VDD_1") (pintype "passive"))
      (node (ref "D27") (pin "1") (pinfunction "VDD_1") (pintype "passive"))
      (node (ref "D28") (pin "1") (pinfunction "VDD_1") (pintype "passive"))
      (node (ref "D29") (pin "1") (pinfunction "VDD_1") (pintype "passive"))
      (node (ref "D3") (pin "1") (pinfunction "VDD_1") (pintype "passive"))
      (node (ref "D30") (pin "1") (pinfunction "VDD_1") (pintype "passive"))
      (node (ref "D31") (pin "1") (pinfunction "VDD_1") (pintype "passive"))
      (node (ref "D32") (pin "1") (pinfunction "VDD_1") (pintype "passive"))
      (node (ref "D33") (pin "1") (pinfunction "VDD_1") (pintype "passive"))
      (node (ref "D34") (pin "1") (pinfunction "VDD_1") (pintype "passive"))
      (node (ref "D35") (pin "1") (pinfunction "VDD_1") (pintype "passive"))
      (node (ref "D36") (pin "1") (pinfunction "VDD_1") (pintype "passive"))
      (node (ref "D37") (pin "1") (pinfunction "VDD_1") (pintype "passive"))
      (node (ref "D38") (pin "1") (pinfunction "VDD_1") (pintype "passive"))
      (node (ref "D39") (pin "1") (pinfunction "VDD_1") (pintype "passive"))
      (node (ref "D4") (pin "1") (pinfunction "VDD_1") (pintype "passive"))
      (node (ref "D40") (pin "1") (pinfunction "VDD_1") (pintype "passive"))
      (node (ref "D41") (pin "1") (pinfunction "VDD_1") (pintype "passive"))
      (node (ref "D42") (pin "1") (pinfunction "VDD_1") (pintype "passive"))
      (node (ref "D43") (pin "1") (pinfunction "VDD_1") (pintype "passive"))
      (node (ref "D44") (pin "1") (pinfunction "VDD_1") (pintype "passive"))
      (node (ref "D45") (pin "1") (pinfunction "VDD_1") (pintype "passive"))
      (node (ref "D46") (pin "1") (pinfunction "VDD_1") (pintype "passive"))
      (node (ref "D47") (pin "1") (pinfunction "VDD_1") (pintype "passive"))
      (node (ref "D48") (pin "1") (pinfunction "VDD_1") (pintype "passive"))
      (node (ref "D49") (pin "1") (pinfunction "VDD_1") (pintype "passive"))
      (node (ref "D5") (pin "1") (pinfunction "VDD_1") (pintype "passive"))
      (node (ref "D6") (pin "1") (pinfunction "VDD_1") (pintype "passive"))
      (node (ref "D7") (pin "1") (pinfunction "VDD_1") (pintype "passive"))
      (node (ref "D8") (pin "1") (pinfunction "VDD_1") (pintype "passive"))
      (node (ref "D9") (pin "1") (pinfunction "VDD_1") (pintype "passive"))
    )
    (net (code "101") (name "unconnected-(D49-CKO-Pad2)") (class "Default")
      (node (ref "D49") (pin "2") (pinfunction "CKO_2") (pintype "passive"))
    )
    (net (code "102") (name "unconnected-(D49-SDO-Pad3)") (class "Default")
      (node (ref "D49") (pin "3") (pinfunction "SDO_3") (pintype "passive"))
    )
  )
)
